# EasyEDA_Schematic_Source_File.net
KiCad netlist of a schematic drawn in EasyEDA
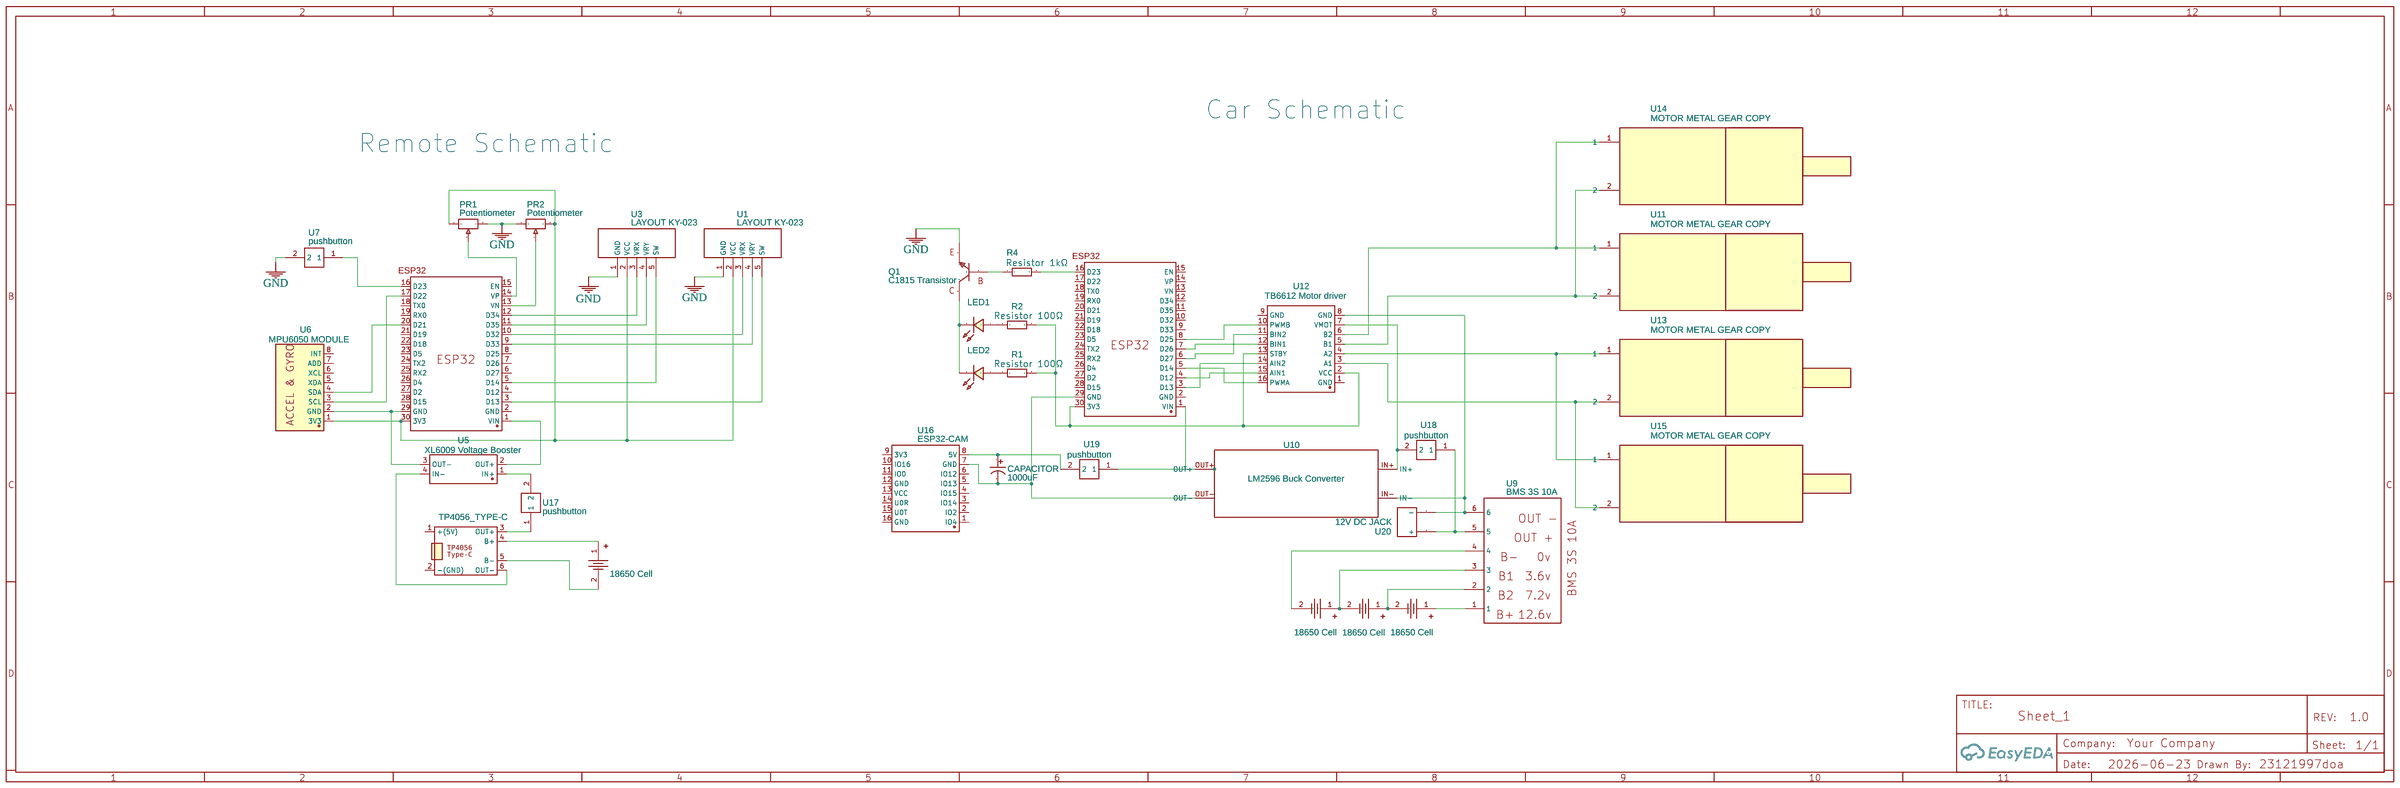
[diagram p0: schematic sheet]

(export (version "E")
  (design (tool "Eeschema 10.0.6"))
  (components
    (comp (ref "B1") (value "18650 Cell") (libsource (lib "") (part "18650 Cell")))
    (comp (ref "B2") (value "18650 Cell") (libsource (lib "") (part "18650 Cell_1")))
    (comp (ref "B3") (value "18650 Cell") (libsource (lib "") (part "18650 Cell_1")))
    (comp (ref "B4") (value "18650 Cell") (libsource (lib "") (part "18650 Cell_1")))
    (comp (ref "CAPACITOR")
      (value "1000uF")
      (fields (field (name "Manufacturer Part") "1000uF 25V") (field (name "Manufacturer") "ValuePro"))
      (libsource (lib "") (part "1000uF 25V"))
    )
    (comp (ref "LED1")
      (value "LED-0603_R")
      (fields
        (field (name "Manufacturer Part") "19-217/R6C-AL1M2VY/3T")
        (field (name "Manufacturer") "EVERLIGHT(台湾亿光)")
      )
      (libsource (lib "") (part "LED-0603_R"))
    )
    (comp (ref "LED2")
      (value "LED-0603_R")
      (fields
        (field (name "Manufacturer Part") "19-217/R6C-AL1M2VY/3T")
        (field (name "Manufacturer") "EVERLIGHT(台湾亿光)")
      )
      (libsource (lib "") (part "LED-0603_R"))
    )
    (comp (ref "PR1")
      (value "Potentiometer")
      (fields
        (field (name "Manufacturer Part") "Potentiometer WH160-1-104")
        (field (name "Manufacturer") "JML")
      )
      (libsource (lib "") (part "Potentiometer copy"))
    )
    (comp (ref "PR2")
      (value "Potentiometer")
      (fields
        (field (name "Manufacturer Part") "Potentiometer WH160-1-104")
        (field (name "Manufacturer") "JML")
      )
      (libsource (lib "") (part "Potentiometer copy"))
    )
    (comp (ref "Q1") (value "C1815 Transistor") (libsource (lib "") (part "Q_2SC1815")))
    (comp (ref "R1")
      (value "Resistor 100Ω")
      (fields (field (name "Manufacturer Part") "MG") (field (name "Manufacturer") "ResistorToday"))
      (libsource (lib "") (part "Resistor_Hole_SMD"))
    )
    (comp (ref "R2")
      (value "Resistor 100Ω")
      (fields (field (name "Manufacturer Part") "MG") (field (name "Manufacturer") "ResistorToday"))
      (libsource (lib "") (part "Resistor_Hole_SMD"))
    )
    (comp (ref "R4")
      (value "Resistor 1kΩ")
      (fields (field (name "Manufacturer Part") "MG") (field (name "Manufacturer") "ResistorToday"))
      (libsource (lib "") (part "Resistor_Hole_SMD"))
    )
    (comp (ref "U1") (value "LAYOUT KY-023") (libsource (lib "") (part "LAYOUT KY-023")))
    (comp (ref "U2") (value "ESP_WROOM_32_30PIN") (libsource (lib "") (part "ESP_WROOM_32_30PIN")))
    (comp (ref "U3") (value "LAYOUT KY-023") (libsource (lib "") (part "LAYOUT KY-023")))
    (comp (ref "U4") (value "TP4056_TYPE-C") (libsource (lib "") (part "TP4056_TYPE-C")))
    (comp (ref "U5")
      (value "XL6009 Voltage Booster")
      (fields (field (name "Manufacturer Part") "xl6009模块"))
      (libsource (lib "") (part "XL6009模块"))
    )
    (comp (ref "U6")
      (value "MPU6050 MODULE")
      (fields (field (name "Manufacturer Part") "MPU6050"))
      (libsource (lib "") (part "MPU6050 MODULE"))
    )
    (comp (ref "U7") (value "pushbutton") (libsource (lib "") (part "pushbutton")))
    (comp (ref "U8") (value "ESP_WROOM_32_30PIN") (libsource (lib "") (part "ESP_WROOM_32_30PIN")))
    (comp (ref "U9")
      (value "BMS 3S 10A")
      (fields (field (name "Manufacturer") "Generic"))
      (libsource (lib "") (part "BMS 3S 10A"))
    )
    (comp (ref "U10") (value "LM2596 Buck Converter") (libsource (lib "") (part "LM2596")))
    (comp (ref "U11") (value "MOTOR METAL GEAR COPY") (libsource (lib "") (part "MOTOR METAL GEAR COPY")))
    (comp (ref "U12") (value "TB6612 Motor driver") (libsource (lib "") (part "TB6612FNG")))
    (comp (ref "U13") (value "MOTOR METAL GEAR COPY") (libsource (lib "") (part "MOTOR METAL GEAR COPY")))
    (comp (ref "U14") (value "MOTOR METAL GEAR COPY") (libsource (lib "") (part "MOTOR METAL GEAR COPY")))
    (comp (ref "U15") (value "MOTOR METAL GEAR COPY") (libsource (lib "") (part "MOTOR METAL GEAR COPY")))
    (comp (ref "U16")
      (value "ESP32-CAM")
      (fields (field (name "Manufacturer") "Ai-Thinker(安信可)"))
      (libsource (lib "") (part "ESP32-CAM"))
    )
    (comp (ref "U17") (value "pushbutton") (libsource (lib "") (part "pushbutton_1")))
    (comp (ref "U18") (value "pushbutton") (libsource (lib "") (part "pushbutton")))
    (comp (ref "U19") (value "pushbutton") (libsource (lib "") (part "pushbutton")))
    (comp (ref "U20") (value "12V DC JACK") (libsource (lib "") (part "12V DC JACK")))
  )
  (nets
    (net (code "1") (name "GND") (class "Default")
      (node (ref "PR1") (pin "1") (pinfunction "1_1") (pintype "input"))
      (node (ref "PR2") (pin "3") (pinfunction "3_3") (pintype "input"))
      (node (ref "Q1") (pin "E") (pinfunction "E_E") (pintype "unspecified"))
      (node (ref "U1") (pin "1") (pinfunction "GND_1") (pintype "unspecified"))
      (node (ref "U3") (pin "1") (pinfunction "GND_1") (pintype "unspecified"))
      (node (ref "U7") (pin "2") (pinfunction "2_2") (pintype "unspecified"))
    )
    (net (code "2") (name "Net-(B2-Pad1)") (class "Default")
      (node (ref "B2") (pin "1") (pinfunction "1_1") (pintype "unspecified"))
      (node (ref "B3") (pin "2") (pinfunction "2_2") (pintype "unspecified"))
      (node (ref "U9") (pin "3") (pinfunction "3_3") (pintype "unspecified"))
    )
    (net (code "3") (name "Net-(B2-Pad2)") (class "Default")
      (node (ref "B2") (pin "2") (pinfunction "2_2") (pintype "unspecified"))
      (node (ref "U9") (pin "4") (pinfunction "4_4") (pintype "unspecified"))
    )
    (net (code "4") (name "Net-(B3-Pad1)") (class "Default")
      (node (ref "B3") (pin "1") (pinfunction "1_1") (pintype "unspecified"))
      (node (ref "B4") (pin "2") (pinfunction "2_2") (pintype "unspecified"))
      (node (ref "U9") (pin "2") (pinfunction "2_2") (pintype "unspecified"))
    )
    (net (code "5") (name "Net-(B4-Pad1)") (class "Default")
      (node (ref "B4") (pin "1") (pinfunction "1_1") (pintype "unspecified"))
      (node (ref "U9") (pin "1") (pinfunction "1_1") (pintype "unspecified"))
    )
    (net (code "6") (name "Net-(CAPACITOR-Pad2)") (class "Default")
      (node (ref "CAPACITOR") (pin "2") (pinfunction "2_2") (pintype "input"))
      (node (ref "U10") (pin "OUT-") (pinfunction "OUT-_OUT-") (pintype "unspecified"))
      (node (ref "U16") (pin "7") (pinfunction "GND_7") (pintype "unspecified"))
      (node (ref "U8") (pin "29") (pinfunction "GND_29") (pintype "unspecified"))
    )
    (net (code "7") (name "Net-(LED1-Pad1)") (class "Default")
      (node (ref "LED1") (pin "1") (pinfunction "1_1") (pintype "unspecified"))
      (node (ref "R2") (pin "1") (pinfunction "1_1") (pintype "unspecified"))
    )
    (net (code "8") (name "Net-(LED1-Pad2)") (class "Default")
      (node (ref "LED1") (pin "2") (pinfunction "2_2") (pintype "unspecified"))
      (node (ref "LED2") (pin "2") (pinfunction "2_2") (pintype "unspecified"))
      (node (ref "Q1") (pin "C") (pinfunction "C_C") (pintype "unspecified"))
    )
    (net (code "9") (name "Net-(LED2-Pad1)") (class "Default")
      (node (ref "LED2") (pin "1") (pinfunction "1_1") (pintype "unspecified"))
      (node (ref "R1") (pin "1") (pinfunction "1_1") (pintype "unspecified"))
    )
    (net (code "10") (name "Net-(Q1-PadB)") (class "Default")
      (node (ref "Q1") (pin "B") (pinfunction "B_B") (pintype "unspecified"))
      (node (ref "R4") (pin "1") (pinfunction "1_1") (pintype "unspecified"))
    )
    (net (code "11") (name "Net-(U1-SW)") (class "Default")
      (node (ref "U1") (pin "5") (pinfunction "SW_5") (pintype "unspecified"))
      (node (ref "U2") (pin "3") (pinfunction "D13_3") (pintype "unspecified"))
    )
    (net (code "12") (name "Net-(U1-VCC)") (class "Default")
      (node (ref "PR1") (pin "3") (pinfunction "3_3") (pintype "input"))
      (node (ref "PR2") (pin "1") (pinfunction "1_1") (pintype "input"))
      (node (ref "U1") (pin "2") (pinfunction "VCC_2") (pintype "unspecified"))
      (node (ref "U2") (pin "30") (pinfunction "3V3_30") (pintype "unspecified"))
      (node (ref "U3") (pin "2") (pinfunction "VCC_2") (pintype "unspecified"))
      (node (ref "U6") (pin "1") (pinfunction "3V3_1") (pintype "unspecified"))
    )
    (net (code "13") (name "Net-(U1-VRX)") (class "Default")
      (node (ref "U1") (pin "3") (pinfunction "VRX_3") (pintype "unspecified"))
      (node (ref "U2") (pin "10") (pinfunction "D32_10") (pintype "unspecified"))
    )
    (net (code "14") (name "Net-(U1-VRY)") (class "Default")
      (node (ref "U1") (pin "4") (pinfunction "VRY_4") (pintype "unspecified"))
      (node (ref "U2") (pin "9") (pinfunction "D33_9") (pintype "unspecified"))
    )
    (net (code "15") (name "Net-(U2-D14)") (class "Default")
      (node (ref "U2") (pin "5") (pinfunction "D14_5") (pintype "unspecified"))
      (node (ref "U3") (pin "5") (pinfunction "SW_5") (pintype "unspecified"))
    )
    (net (code "16") (name "Net-(U2-D21)") (class "Default")
      (node (ref "U2") (pin "20") (pinfunction "D21_20") (pintype "unspecified"))
      (node (ref "U6") (pin "4") (pinfunction "SDA_4") (pintype "unspecified"))
    )
    (net (code "17") (name "Net-(U2-D22)") (class "Default")
      (node (ref "U2") (pin "17") (pinfunction "D22_17") (pintype "unspecified"))
      (node (ref "U6") (pin "3") (pinfunction "SCL_3") (pintype "unspecified"))
    )
    (net (code "18") (name "Net-(U2-D23)") (class "Default")
      (node (ref "U2") (pin "16") (pinfunction "D23_16") (pintype "unspecified"))
      (node (ref "U7") (pin "1") (pinfunction "1_1") (pintype "unspecified"))
    )
    (net (code "19") (name "Net-(U2-D34)") (class "Default")
      (node (ref "U2") (pin "12") (pinfunction "D34_12") (pintype "unspecified"))
      (node (ref "U3") (pin "3") (pinfunction "VRX_3") (pintype "unspecified"))
    )
    (net (code "20") (name "Net-(U2-D35)") (class "Default")
      (node (ref "U2") (pin "11") (pinfunction "D35_11") (pintype "unspecified"))
      (node (ref "U3") (pin "4") (pinfunction "VRY_4") (pintype "unspecified"))
    )
    (net (code "21") (name "Net-(U2-VIN)") (class "Default")
      (node (ref "U2") (pin "1") (pinfunction "VIN_1") (pintype "unspecified"))
      (node (ref "U5") (pin "2") (pinfunction "OUT+_2") (pintype "unspecified"))
    )
    (net (code "22") (name "Net-(U2-VN)") (class "Default")
      (node (ref "PR2") (pin "2") (pinfunction "2_2") (pintype "input"))
      (node (ref "U2") (pin "13") (pinfunction "VN_13") (pintype "unspecified"))
    )
    (net (code "23") (name "Net-(U2-VP)") (class "Default")
      (node (ref "PR1") (pin "2") (pinfunction "2_2") (pintype "input"))
      (node (ref "U2") (pin "14") (pinfunction "VP_14") (pintype "unspecified"))
    )
    (net (code "24") (name "Net-(U4-B+)") (class "Default")
      (node (ref "B1") (pin "1") (pinfunction "1_1") (pintype "unspecified"))
      (node (ref "U4") (pin "4") (pinfunction "B+_4") (pintype "unspecified"))
    )
    (net (code "25") (name "Net-(U4-B-)") (class "Default")
      (node (ref "B1") (pin "2") (pinfunction "2_2") (pintype "unspecified"))
      (node (ref "U4") (pin "5") (pinfunction "B-_5") (pintype "unspecified"))
    )
    (net (code "26") (name "Net-(U4-OUT+)") (class "Default")
      (node (ref "U17") (pin "1") (pinfunction "1_1") (pintype "unspecified"))
      (node (ref "U4") (pin "3") (pinfunction "OUT+_3") (pintype "unspecified"))
    )
    (net (code "27") (name "Net-(U4-OUT-)") (class "Default")
      (node (ref "U4") (pin "6") (pinfunction "OUT-_6") (pintype "unspecified"))
      (node (ref "U5") (pin "4") (pinfunction "IN-_4") (pintype "unspecified"))
    )
    (net (code "28") (name "Net-(U5-IN+)") (class "Default")
      (node (ref "U17") (pin "2") (pinfunction "2_2") (pintype "unspecified"))
      (node (ref "U5") (pin "1") (pinfunction "IN+_1") (pintype "unspecified"))
    )
    (net (code "29") (name "Net-(U5-OUT-)") (class "Default")
      (node (ref "U2") (pin "29") (pinfunction "GND_29") (pintype "unspecified"))
      (node (ref "U5") (pin "3") (pinfunction "OUT-_3") (pintype "unspecified"))
      (node (ref "U6") (pin "2") (pinfunction "GND_2") (pintype "unspecified"))
    )
    (net (code "30") (name "Net-(U8-D23)") (class "Default")
      (node (ref "R4") (pin "2") (pinfunction "2_2") (pintype "unspecified"))
      (node (ref "U8") (pin "16") (pinfunction "D23_16") (pintype "unspecified"))
    )
    (net (code "31") (name "Net-(U8-VIN)") (class "Default")
      (node (ref "U10") (pin "OUT+") (pinfunction "OUT+_OUT+") (pintype "unspecified"))
      (node (ref "U19") (pin "1") (pinfunction "1_1") (pintype "unspecified"))
      (node (ref "U8") (pin "1") (pinfunction "VIN_1") (pintype "unspecified"))
    )
    (net (code "32") (name "Net-(U12-A1)") (class "Default")
      (node (ref "U12") (pin "3") (pinfunction "A1_3") (pintype "unspecified"))
      (node (ref "U13") (pin "2") (pinfunction "2_2") (pintype "unspecified"))
      (node (ref "U15") (pin "2") (pinfunction "2_2") (pintype "unspecified"))
    )
    (net (code "33") (name "Net-(U12-A2)") (class "Default")
      (node (ref "U12") (pin "4") (pinfunction "A2_4") (pintype "unspecified"))
      (node (ref "U13") (pin "1") (pinfunction "1_1") (pintype "unspecified"))
      (node (ref "U15") (pin "1") (pinfunction "1_1") (pintype "unspecified"))
    )
    (net (code "34") (name "Net-(U12-AIN1)") (class "Default")
      (node (ref "U12") (pin "15") (pinfunction "AIN1_15") (pintype "unspecified"))
      (node (ref "U8") (pin "4") (pinfunction "D12_4") (pintype "unspecified"))
    )
    (net (code "35") (name "Net-(U12-AIN2)") (class "Default")
      (node (ref "U12") (pin "14") (pinfunction "AIN2_14") (pintype "unspecified"))
      (node (ref "U8") (pin "3") (pinfunction "D13_3") (pintype "unspecified"))
    )
    (net (code "36") (name "Net-(U12-B1)") (class "Default")
      (node (ref "U11") (pin "2") (pinfunction "2_2") (pintype "unspecified"))
      (node (ref "U12") (pin "5") (pinfunction "B1_5") (pintype "unspecified"))
      (node (ref "U14") (pin "2") (pinfunction "2_2") (pintype "unspecified"))
    )
    (net (code "37") (name "Net-(U12-B2)") (class "Default")
      (node (ref "U11") (pin "1") (pinfunction "1_1") (pintype "unspecified"))
      (node (ref "U12") (pin "6") (pinfunction "B2_6") (pintype "unspecified"))
      (node (ref "U14") (pin "1") (pinfunction "1_1") (pintype "unspecified"))
    )
    (net (code "38") (name "Net-(U12-BIN1)") (class "Default")
      (node (ref "U12") (pin "12") (pinfunction "BIN1_12") (pintype "unspecified"))
      (node (ref "U8") (pin "7") (pinfunction "D26_7") (pintype "unspecified"))
    )
    (net (code "39") (name "Net-(U12-BIN2)") (class "Default")
      (node (ref "U12") (pin "11") (pinfunction "BIN2_11") (pintype "unspecified"))
      (node (ref "U8") (pin "6") (pinfunction "D27_6") (pintype "unspecified"))
    )
    (net (code "40") (name "Net-(U12-PWMA)") (class "Default")
      (node (ref "U12") (pin "16") (pinfunction "PWMA_16") (pintype "unspecified"))
      (node (ref "U8") (pin "5") (pinfunction "D14_5") (pintype "unspecified"))
    )
    (net (code "41") (name "Net-(U12-PWMB)") (class "Default")
      (node (ref "U12") (pin "10") (pinfunction "PWMB_10") (pintype "unspecified"))
      (node (ref "U8") (pin "8") (pinfunction "D25_8") (pintype "unspecified"))
    )
    (net (code "42") (name "Net-(U12-STBY)") (class "Default")
      (node (ref "R1") (pin "2") (pinfunction "2_2") (pintype "unspecified"))
      (node (ref "R2") (pin "2") (pinfunction "2_2") (pintype "unspecified"))
      (node (ref "U12") (pin "13") (pinfunction "STBY_13") (pintype "unspecified"))
      (node (ref "U12") (pin "2") (pinfunction "VCC_2") (pintype "unspecified"))
      (node (ref "U8") (pin "30") (pinfunction "3V3_30") (pintype "unspecified"))
    )
    (net (code "43") (name "Net-(U12-VMOT)") (class "Default")
      (node (ref "U10") (pin "IN+") (pinfunction "IN+_IN+") (pintype "unspecified"))
      (node (ref "U12") (pin "7") (pinfunction "VMOT_7") (pintype "unspecified"))
      (node (ref "U18") (pin "2") (pinfunction "2_2") (pintype "unspecified"))
    )
    (net (code "44") (name "Net-(U16-5V)") (class "Default")
      (node (ref "CAPACITOR") (pin "1") (pinfunction "1_1") (pintype "input"))
      (node (ref "U16") (pin "8") (pinfunction "5V_8") (pintype "unspecified"))
      (node (ref "U19") (pin "2") (pinfunction "2_2") (pintype "unspecified"))
    )
    (net (code "45") (name "Net-(U20-+)") (class "Default")
      (node (ref "U18") (pin "1") (pinfunction "1_1") (pintype "unspecified"))
      (node (ref "U20") (pin "Vcc") (pinfunction "+_Vcc") (pintype "unspecified"))
      (node (ref "U9") (pin "5") (pinfunction "5_5") (pintype "unspecified"))
    )
    (net (code "46") (name "Net-(U20--)") (class "Default")
      (node (ref "U10") (pin "IN-") (pinfunction "IN-_IN-") (pintype "unspecified"))
      (node (ref "U12") (pin "8") (pinfunction "GND_8") (pintype "unspecified"))
      (node (ref "U20") (pin "GND") (pinfunction "-_GND") (pintype "unspecified"))
      (node (ref "U9") (pin "6") (pinfunction "6_6") (pintype "unspecified"))
    )
    (net (code "47") (name "unconnected-(U2-D2-Pad27)") (class "Default")
      (node (ref "U2") (pin "27") (pinfunction "D2_27") (pintype "unspecified"))
    )
    (net (code "48") (name "unconnected-(U2-D4-Pad26)") (class "Default")
      (node (ref "U2") (pin "26") (pinfunction "D4_26") (pintype "unspecified"))
    )
    (net (code "49") (name "unconnected-(U2-D5-Pad23)") (class "Default")
      (node (ref "U2") (pin "23") (pinfunction "D5_23") (pintype "unspecified"))
    )
    (net (code "50") (name "unconnected-(U2-D12-Pad4)") (class "Default")
      (node (ref "U2") (pin "4") (pinfunction "D12_4") (pintype "unspecified"))
    )
    (net (code "51") (name "unconnected-(U2-D15-Pad28)") (class "Default")
      (node (ref "U2") (pin "28") (pinfunction "D15_28") (pintype "unspecified"))
    )
    (net (code "52") (name "unconnected-(U2-D18-Pad22)") (class "Default")
      (node (ref "U2") (pin "22") (pinfunction "D18_22") (pintype "unspecified"))
    )
    (net (code "53") (name "unconnected-(U2-D19-Pad21)") (class "Default")
      (node (ref "U2") (pin "21") (pinfunction "D19_21") (pintype "unspecified"))
    )
    (net (code "54") (name "unconnected-(U2-D25-Pad8)") (class "Default")
      (node (ref "U2") (pin "8") (pinfunction "D25_8") (pintype "unspecified"))
    )
    (net (code "55") (name "unconnected-(U2-D26-Pad7)") (class "Default")
      (node (ref "U2") (pin "7") (pinfunction "D26_7") (pintype "unspecified"))
    )
    (net (code "56") (name "unconnected-(U2-D27-Pad6)") (class "Default")
      (node (ref "U2") (pin "6") (pinfunction "D27_6") (pintype "unspecified"))
    )
    (net (code "57") (name "unconnected-(U2-EN-Pad15)") (class "Default")
      (node (ref "U2") (pin "15") (pinfunction "EN_15") (pintype "unspecified"))
    )
    (net (code "58") (name "unconnected-(U2-GND-Pad2)") (class "Default")
      (node (ref "U2") (pin "2") (pinfunction "GND_2") (pintype "unspecified"))
    )
    (net (code "59") (name "unconnected-(U2-RX0-Pad19)") (class "Default")
      (node (ref "U2") (pin "19") (pinfunction "RX0_19") (pintype "unspecified"))
    )
    (net (code "60") (name "unconnected-(U2-RX2-Pad25)") (class "Default")
      (node (ref "U2") (pin "25") (pinfunction "RX2_25") (pintype "unspecified"))
    )
    (net (code "61") (name "unconnected-(U2-TX0-Pad18)") (class "Default")
      (node (ref "U2") (pin "18") (pinfunction "TX0_18") (pintype "unspecified"))
    )
    (net (code "62") (name "unconnected-(U2-TX2-Pad24)") (class "Default")
      (node (ref "U2") (pin "24") (pinfunction "TX2_24") (pintype "unspecified"))
    )
    (net (code "63") (name "unconnected-(U4-+(5V)-Pad1)") (class "Default")
      (node (ref "U4") (pin "1") (pinfunction "+(5V)_1") (pintype "unspecified"))
    )
    (net (code "64") (name "unconnected-(U4--(GND)-Pad2)") (class "Default")
      (node (ref "U4") (pin "2") (pinfunction "-(GND)_2") (pintype "unspecified"))
    )
    (net (code "65") (name "unconnected-(U6-ADD-Pad7)") (class "Default")
      (node (ref "U6") (pin "7") (pinfunction "ADD_7") (pintype "unspecified"))
    )
    (net (code "66") (name "unconnected-(U6-INT-Pad8)") (class "Default")
      (node (ref "U6") (pin "8") (pinfunction "INT_8") (pintype "unspecified"))
    )
    (net (code "67") (name "unconnected-(U6-XCL-Pad6)") (class "Default")
      (node (ref "U6") (pin "6") (pinfunction "XCL_6") (pintype "unspecified"))
    )
    (net (code "68") (name "unconnected-(U6-XDA-Pad5)") (class "Default")
      (node (ref "U6") (pin "5") (pinfunction "XDA_5") (pintype "unspecified"))
    )
    (net (code "69") (name "unconnected-(U8-D2-Pad27)") (class "Default")
      (node (ref "U8") (pin "27") (pinfunction "D2_27") (pintype "unspecified"))
    )
    (net (code "70") (name "unconnected-(U8-D4-Pad26)") (class "Default")
      (node (ref "U8") (pin "26") (pinfunction "D4_26") (pintype "unspecified"))
    )
    (net (code "71") (name "unconnected-(U8-D5-Pad23)") (class "Default")
      (node (ref "U8") (pin "23") (pinfunction "D5_23") (pintype "unspecified"))
    )
    (net (code "72") (name "unconnected-(U8-D15-Pad28)") (class "Default")
      (node (ref "U8") (pin "28") (pinfunction "D15_28") (pintype "unspecified"))
    )
    (net (code "73") (name "unconnected-(U8-D18-Pad22)") (class "Default")
      (node (ref "U8") (pin "22") (pinfunction "D18_22") (pintype "unspecified"))
    )
    (net (code "74") (name "unconnected-(U8-D19-Pad21)") (class "Default")
      (node (ref "U8") (pin "21") (pinfunction "D19_21") (pintype "unspecified"))
    )
    (net (code "75") (name "unconnected-(U8-D21-Pad20)") (class "Default")
      (node (ref "U8") (pin "20") (pinfunction "D21_20") (pintype "unspecified"))
    )
    (net (code "76") (name "unconnected-(U8-D22-Pad17)") (class "Default")
      (node (ref "U8") (pin "17") (pinfunction "D22_17") (pintype "unspecified"))
    )
    (net (code "77") (name "unconnected-(U8-D32-Pad10)") (class "Default")
      (node (ref "U8") (pin "10") (pinfunction "D32_10") (pintype "unspecified"))
    )
    (net (code "78") (name "unconnected-(U8-D33-Pad9)") (class "Default")
      (node (ref "U8") (pin "9") (pinfunction "D33_9") (pintype "unspecified"))
    )
    (net (code "79") (name "unconnected-(U8-D34-Pad12)") (class "Default")
      (node (ref "U8") (pin "12") (pinfunction "D34_12") (pintype "unspecified"))
    )
    (net (code "80") (name "unconnected-(U8-D35-Pad11)") (class "Default")
      (node (ref "U8") (pin "11") (pinfunction "D35_11") (pintype "unspecified"))
    )
    (net (code "81") (name "unconnected-(U8-EN-Pad15)") (class "Default")
      (node (ref "U8") (pin "15") (pinfunction "EN_15") (pintype "unspecified"))
    )
    (net (code "82") (name "unconnected-(U8-GND-Pad2)") (class "Default")
      (node (ref "U8") (pin "2") (pinfunction "GND_2") (pintype "unspecified"))
    )
    (net (code "83") (name "unconnected-(U8-RX0-Pad19)") (class "Default")
      (node (ref "U8") (pin "19") (pinfunction "RX0_19") (pintype "unspecified"))
    )
    (net (code "84") (name "unconnected-(U8-RX2-Pad25)") (class "Default")
      (node (ref "U8") (pin "25") (pinfunction "RX2_25") (pintype "unspecified"))
    )
    (net (code "85") (name "unconnected-(U8-TX0-Pad18)") (class "Default")
      (node (ref "U8") (pin "18") (pinfunction "TX0_18") (pintype "unspecified"))
    )
    (net (code "86") (name "unconnected-(U8-TX2-Pad24)") (class "Default")
      (node (ref "U8") (pin "24") (pinfunction "TX2_24") (pintype "unspecified"))
    )
    (net (code "87") (name "unconnected-(U8-VN-Pad13)") (class "Default")
      (node (ref "U8") (pin "13") (pinfunction "VN_13") (pintype "unspecified"))
    )
    (net (code "88") (name "unconnected-(U8-VP-Pad14)") (class "Default")
      (node (ref "U8") (pin "14") (pinfunction "VP_14") (pintype "unspecified"))
    )
    (net (code "89") (name "unconnected-(U12-GND-Pad1)") (class "Default")
      (node (ref "U12") (pin "1") (pinfunction "GND_1") (pintype "unspecified"))
    )
    (net (code "90") (name "unconnected-(U12-GND-Pad9)") (class "Default")
      (node (ref "U12") (pin "9") (pinfunction "GND_9") (pintype "unspecified"))
    )
    (net (code "91") (name "unconnected-(U16-3V3-Pad9)") (class "Default")
      (node (ref "U16") (pin "9") (pinfunction "3V3_9") (pintype "unspecified"))
    )
    (net (code "92") (name "unconnected-(U16-GND-Pad12)") (class "Default")
      (node (ref "U16") (pin "12") (pinfunction "GND_12") (pintype "unspecified"))
    )
    (net (code "93") (name "unconnected-(U16-GND-Pad16)") (class "Default")
      (node (ref "U16") (pin "16") (pinfunction "GND_16") (pintype "unspecified"))
    )
    (net (code "94") (name "unconnected-(U16-IO0-Pad11)") (class "Default")
      (node (ref "U16") (pin "11") (pinfunction "IO0_11") (pintype "unspecified"))
    )
    (net (code "95") (name "unconnected-(U16-IO2-Pad2)") (class "Default")
      (node (ref "U16") (pin "2") (pinfunction "IO2_2") (pintype "unspecified"))
    )
    (net (code "96") (name "unconnected-(U16-IO4-Pad1)") (class "Default")
      (node (ref "U16") (pin "1") (pinfunction "IO4_1") (pintype "unspecified"))
    )
    (net (code "97") (name "unconnected-(U16-IO12-Pad6)") (class "Default")
      (node (ref "U16") (pin "6") (pinfunction "IO12_6") (pintype "unspecified"))
    )
    (net (code "98") (name "unconnected-(U16-IO13-Pad5)") (class "Default")
      (node (ref "U16") (pin "5") (pinfunction "IO13_5") (pintype "unspecified"))
    )
    (net (code "99") (name "unconnected-(U16-IO14-Pad3)") (class "Default")
      (node (ref "U16") (pin "3") (pinfunction "IO14_3") (pintype "unspecified"))
    )
    (net (code "100") (name "unconnected-(U16-IO15-Pad4)") (class "Default")
      (node (ref "U16") (pin "4") (pinfunction "IO15_4") (pintype "unspecified"))
    )
    (net (code "101") (name "unconnected-(U16-IO16-Pad10)") (class "Default")
      (node (ref "U16") (pin "10") (pinfunction "IO16_10") (pintype "unspecified"))
    )
    (net (code "102") (name "unconnected-(U16-U0R-Pad14)") (class "Default")
      (node (ref "U16") (pin "14") (pinfunction "U0R_14") (pintype "unspecified"))
    )
    (net (code "103") (name "unconnected-(U16-U0T-Pad15)") (class "Default")
      (node (ref "U16") (pin "15") (pinfunction "U0T_15") (pintype "unspecified"))
    )
    (net (code "104") (name "unconnected-(U16-VCC-Pad13)") (class "Default")
      (node (ref "U16") (pin "13") (pinfunction "VCC_13") (pintype "unspecified"))
    )
  )
)
